# REF_TIMING.net
KiCad netlist of a schematic drawn in Altium Designer
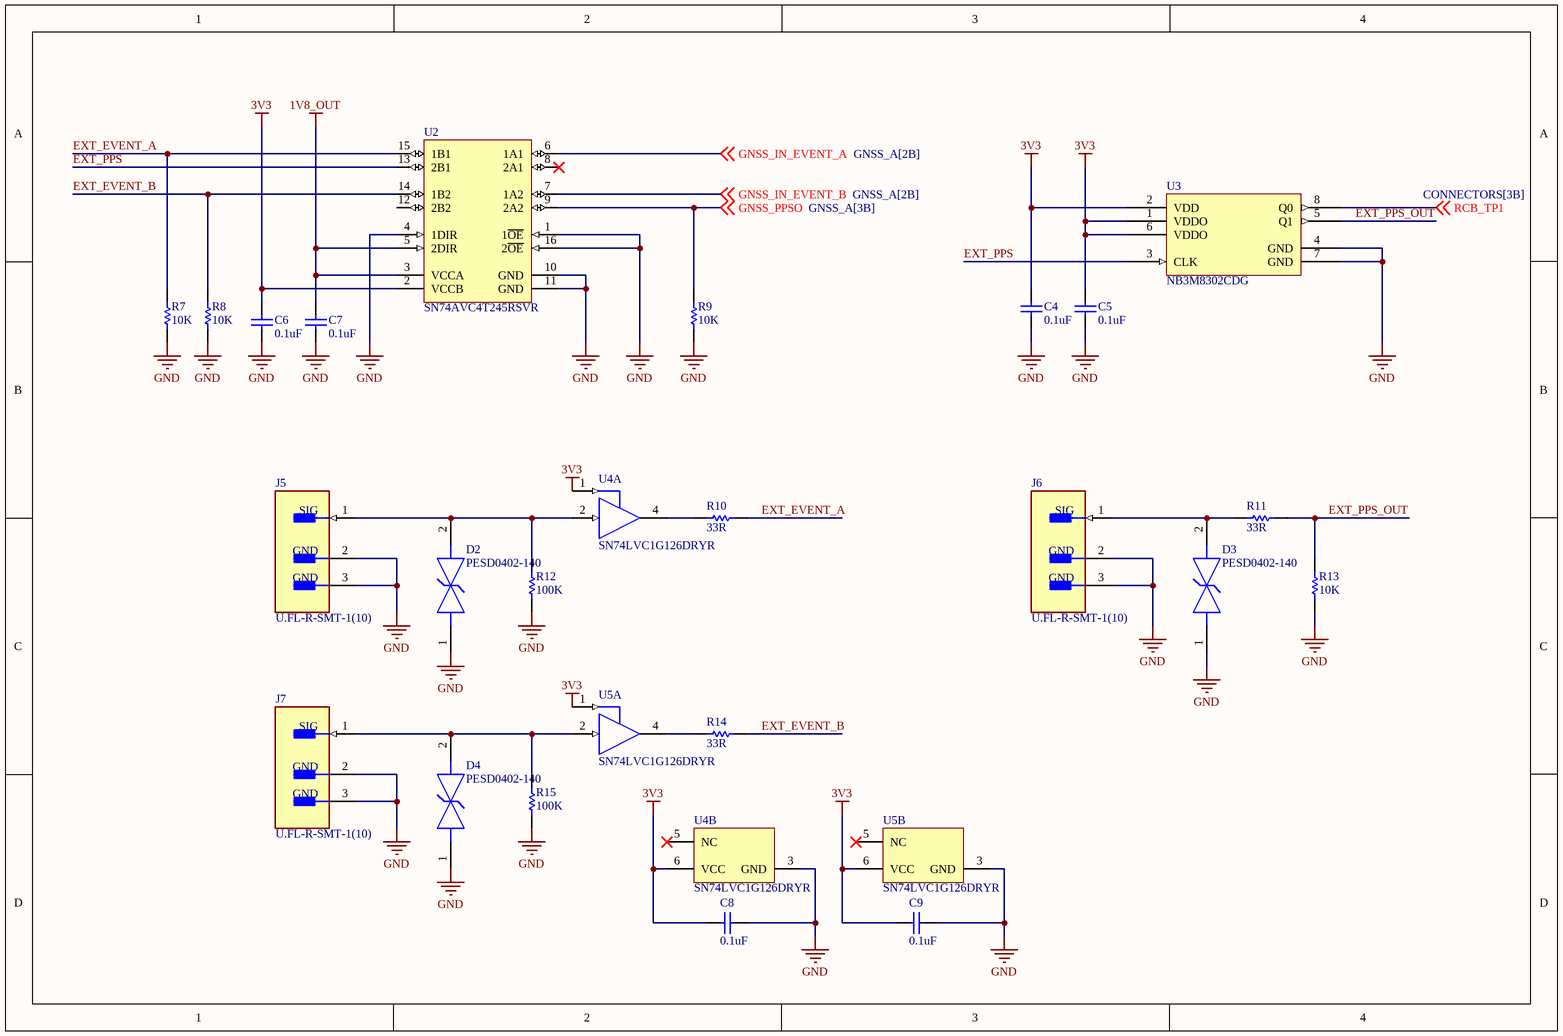
[diagram p0: REF_TIMING.SchDoc]

(export (version "E")
  (design (tool "Eeschema 10.0.6"))
  (components
    (comp (ref "C4")
      (value "0.1uF")
      (footprint "CAPC1005X56X25LL10T15")
      (fields
        (field (name "MANUFACTURER") "AVX Interconnect / Elco")
        (field (name "PART NUMBER") "04026D104KAT2A")
      )
      (libsource (lib "Altium Content Vault") (part "CAP"))
    )
    (comp (ref "C5")
      (value "0.1uF")
      (footprint "CAPC1005X56X25LL10T15")
      (fields
        (field (name "MANUFACTURER") "AVX Interconnect / Elco")
        (field (name "PART NUMBER") "04026D104KAT2A")
      )
      (libsource (lib "Altium Content Vault") (part "CAP"))
    )
    (comp (ref "C6")
      (value "0.1uF")
      (footprint "CAPC1005X56X25LL10T15")
      (fields
        (field (name "MANUFACTURER") "AVX Interconnect / Elco")
        (field (name "PART NUMBER") "04026D104KAT2A")
      )
      (libsource (lib "Altium Content Vault") (part "CAP"))
    )
    (comp (ref "C7")
      (value "0.1uF")
      (footprint "CAPC1005X56X25LL10T15")
      (fields
        (field (name "MANUFACTURER") "AVX Interconnect / Elco")
        (field (name "PART NUMBER") "04026D104KAT2A")
      )
      (libsource (lib "Altium Content Vault") (part "CAP"))
    )
    (comp (ref "C8")
      (value "0.1uF")
      (footprint "CAPC1005X56X25LL10T15")
      (fields
        (field (name "MANUFACTURER") "AVX Interconnect / Elco")
        (field (name "PART NUMBER") "04026D104KAT2A")
      )
      (libsource (lib "Altium Content Vault") (part "CAP"))
    )
    (comp (ref "C9")
      (value "0.1uF")
      (footprint "CAPC1005X56X25LL10T15")
      (fields
        (field (name "MANUFACTURER") "AVX Interconnect / Elco")
        (field (name "PART NUMBER") "04026D104KAT2A")
      )
      (libsource (lib "Altium Content Vault") (part "CAP"))
    )
    (comp (ref "D2")
      (value "PESD0402-140")
      (footprint "FP-PESD0402-MFG")
      (description "TVS DIODE 14V 40V 0402")
      (fields
        (field (name "OCTOPART") "https://octopart.com/pesd0402-140-littelfuse-74215061")
        (field (name "MANUFACTURER") "Littelfuse Inc.")
      )
      (libsource (lib "Altium Content Vault") (part "edccc070dd5cba1f9372128faf3915e"))
    )
    (comp (ref "D3")
      (value "PESD0402-140")
      (footprint "FP-PESD0402-MFG")
      (description "TVS DIODE 14V 40V 0402")
      (fields
        (field (name "OCTOPART") "https://octopart.com/pesd0402-140-littelfuse-74215061")
        (field (name "MANUFACTURER") "Littelfuse Inc.")
      )
      (libsource (lib "Altium Content Vault") (part "edccc070dd5cba1f9372128faf3915e"))
    )
    (comp (ref "D4")
      (value "PESD0402-140")
      (footprint "FP-PESD0402-MFG")
      (description "TVS DIODE 14V 40V 0402")
      (fields
        (field (name "OCTOPART") "https://octopart.com/pesd0402-140-littelfuse-74215061")
        (field (name "MANUFACTURER") "Littelfuse Inc.")
      )
      (libsource (lib "Altium Content Vault") (part "edccc070dd5cba1f9372128faf3915e"))
    )
    (comp (ref "J5")
      (value "U.FL-R-SMT-1(10)")
      (footprint "FP-U_FL-R-SMT-1_10-MFG")
      (description "CONN U.FL RCPT STR 50 OHM SMD")
      (libsource (lib "Altium Content Vault") (part "7158abf7d987fa84906f6fb0d115710"))
    )
    (comp (ref "J6")
      (value "U.FL-R-SMT-1(10)")
      (footprint "FP-U_FL-R-SMT-1_10-MFG")
      (description "CONN U.FL RCPT STR 50 OHM SMD")
      (libsource (lib "Altium Content Vault") (part "7158abf7d987fa84906f6fb0d115710"))
    )
    (comp (ref "J7")
      (value "U.FL-R-SMT-1(10)")
      (footprint "FP-U_FL-R-SMT-1_10-MFG")
      (description "CONN U.FL RCPT STR 50 OHM SMD")
      (libsource (lib "Altium Content Vault") (part "7158abf7d987fa84906f6fb0d115710"))
    )
    (comp (ref "R7")
      (value "10K")
      (footprint "RESC1005X40X25ML05T10")
      (fields (field (name "PART NUMBER") "CRCW040210K0FKEDHP") (field (name "MANUFACTURER") "Vishay Dale"))
      (libsource (lib "Altium Content Vault") (part "RES"))
    )
    (comp (ref "R8")
      (value "10K")
      (footprint "RESC1005X40X25ML05T10")
      (fields (field (name "PART NUMBER") "CRCW040210K0FKEDHP") (field (name "MANUFACTURER") "Vishay Dale"))
      (libsource (lib "Altium Content Vault") (part "RES"))
    )
    (comp (ref "R9")
      (value "10K")
      (footprint "RESC1005X40X25ML05T10")
      (fields (field (name "PART NUMBER") "CRCW040210K0FKEDHP") (field (name "MANUFACTURER") "Vishay Dale"))
      (libsource (lib "Altium Content Vault") (part "RES"))
    )
    (comp (ref "R10")
      (value "33R")
      (footprint "RESC1005X40X25LL05T10")
      (fields (field (name "PART NUMBER") "RC0402FR-0733RL") (field (name "MANUFACTURER") "Yageo / Phycomp"))
      (libsource (lib "Altium Content Vault") (part "RES"))
    )
    (comp (ref "R11")
      (value "33R")
      (footprint "RESC1005X40X25LL05T10")
      (fields (field (name "PART NUMBER") "RC0402FR-0733RL") (field (name "MANUFACTURER") "Yageo / Phycomp"))
      (libsource (lib "Altium Content Vault") (part "RES"))
    )
    (comp (ref "R12")
      (value "100K")
      (footprint "RESC1005X40X25NL05T10")
      (fields (field (name "PART NUMBER") "RC0402FR-07100KL") (field (name "MANUFACTURER") "Yageo / Phycomp"))
      (libsource (lib "Altium Content Vault") (part "RES"))
    )
    (comp (ref "R13")
      (value "10K")
      (footprint "RESC1005X40X25ML05T10")
      (fields (field (name "PART NUMBER") "CRCW040210K0FKEDHP") (field (name "MANUFACTURER") "Vishay Dale"))
      (libsource (lib "Altium Content Vault") (part "RES"))
    )
    (comp (ref "R14")
      (value "33R")
      (footprint "RESC1005X40X25LL05T10")
      (fields (field (name "PART NUMBER") "RC0402FR-0733RL") (field (name "MANUFACTURER") "Yageo / Phycomp"))
      (libsource (lib "Altium Content Vault") (part "RES"))
    )
    (comp (ref "R15")
      (value "100K")
      (footprint "RESC1005X40X25NL05T10")
      (fields (field (name "PART NUMBER") "RC0402FR-07100KL") (field (name "MANUFACTURER") "Yageo / Phycomp"))
      (libsource (lib "Altium Content Vault") (part "RES"))
    )
    (comp (ref "U2")
      (value "SN74AVC4T245RSVR")
      (footprint "RSV0016A_V")
      (fields (field (name "MANUFACTURER") "Texas Instruments"))
      (libsource (lib "Altium Content Vault") (part "TI-SN74AVC4T245-UQFN-16"))
    )
    (comp (ref "U3")
      (value "NB3M8302CDG")
      (footprint "SOIC8_ONS")
      (description "No Description Available")
      (fields (field (name "COPYRIGHT") "Copyright (C) 2023 Ultra Librarian. All rights reserved."))
      (libsource (lib "NB3M8302CDG") (part "NB3M8302CDG"))
    )
    (comp (ref "U4")
      (value "SN74LVC1G126DRYR")
      (footprint "DRY0006A_V")
      (description "Single Bus Buffer Gate With 3-State Outputs, DRY0006A, LARGE T&R")
      (fields
        (field (name "MANUFACTURER") "Texas Instruments")
        (field (name "GENERIC PART NUMBER") "SN74LVC1G126")
      )
      (libsource (lib "Altium Content Vault") (part "TI-SN74XXX1G126-6"))
    )
    (comp (ref "U5")
      (value "SN74LVC1G126DRYR")
      (footprint "DRY0006A_V")
      (description "Single Bus Buffer Gate With 3-State Outputs, DRY0006A, LARGE T&R")
      (fields
        (field (name "MANUFACTURER") "Texas Instruments")
        (field (name "GENERIC PART NUMBER") "SN74LVC1G126")
      )
      (libsource (lib "Altium Content Vault") (part "TI-SN74XXX1G126-6"))
    )
  )
  (nets
    (net (code "1") (name "/EXT_EVENT_A") (class "Default")
      (node (ref "R10") (pin "2") (pinfunction "2_2") (pintype "passive"))
      (node (ref "R7") (pin "2") (pinfunction "2_2") (pintype "passive"))
      (node (ref "U2") (pin "15") (pinfunction "1B1_15") (pintype "bidirectional"))
    )
    (net (code "2") (name "/EXT_EVENT_B") (class "Default")
      (node (ref "R14") (pin "2") (pinfunction "2_2") (pintype "passive"))
      (node (ref "R8") (pin "2") (pinfunction "2_2") (pintype "passive"))
      (node (ref "U2") (pin "14") (pinfunction "1B2_14") (pintype "bidirectional"))
    )
    (net (code "3") (name "/EXT_PPS") (class "Default")
      (node (ref "U2") (pin "13") (pinfunction "2B1_13") (pintype "bidirectional"))
      (node (ref "U3") (pin "3") (pinfunction "CLK_3") (pintype "input"))
    )
    (net (code "4") (name "/EXT_PPS_OUT") (class "Default")
      (node (ref "R11") (pin "2") (pinfunction "2_2") (pintype "passive"))
      (node (ref "R13") (pin "2") (pinfunction "2_2") (pintype "passive"))
      (node (ref "U3") (pin "5") (pinfunction "Q1_5") (pintype "output"))
    )
    (net (code "5") (name "1V8_OUT") (class "Default")
      (node (ref "C7") (pin "2") (pinfunction "2_2") (pintype "passive"))
      (node (ref "U2") (pin "3") (pinfunction "VCCA_3") (pintype "power_in"))
      (node (ref "U2") (pin "5") (pinfunction "2DIR_5") (pintype "input"))
    )
    (net (code "6") (name "3V3") (class "Default")
      (node (ref "C4") (pin "1") (pinfunction "1_1") (pintype "passive"))
      (node (ref "C5") (pin "1") (pinfunction "1_1") (pintype "passive"))
      (node (ref "C6") (pin "2") (pinfunction "2_2") (pintype "passive"))
      (node (ref "C8") (pin "2") (pinfunction "2_2") (pintype "passive"))
      (node (ref "C9") (pin "2") (pinfunction "2_2") (pintype "passive"))
      (node (ref "U2") (pin "2") (pinfunction "VCCB_2") (pintype "power_in"))
      (node (ref "U3") (pin "1") (pinfunction "VDDO_1") (pintype "power_in"))
      (node (ref "U3") (pin "2") (pinfunction "VDD_2") (pintype "power_in"))
      (node (ref "U3") (pin "6") (pinfunction "VDDO_6") (pintype "power_in"))
      (node (ref "U4") (pin "1") (pinfunction "OE_1") (pintype "input"))
      (node (ref "U4") (pin "6") (pinfunction "VCC_6") (pintype "power_in"))
      (node (ref "U5") (pin "1") (pinfunction "OE_1") (pintype "input"))
      (node (ref "U5") (pin "6") (pinfunction "VCC_6") (pintype "power_in"))
    )
    (net (code "7") (name "GND") (class "Default")
      (node (ref "C4") (pin "2") (pinfunction "2_2") (pintype "passive"))
      (node (ref "C5") (pin "2") (pinfunction "2_2") (pintype "passive"))
      (node (ref "C6") (pin "1") (pinfunction "1_1") (pintype "passive"))
      (node (ref "C7") (pin "1") (pinfunction "1_1") (pintype "passive"))
      (node (ref "C8") (pin "1") (pinfunction "1_1") (pintype "passive"))
      (node (ref "C9") (pin "1") (pinfunction "1_1") (pintype "passive"))
      (node (ref "D2") (pin "1") (pinfunction "1_1") (pintype "passive"))
      (node (ref "D3") (pin "1") (pinfunction "1_1") (pintype "passive"))
      (node (ref "D4") (pin "1") (pinfunction "1_1") (pintype "passive"))
      (node (ref "J5") (pin "2") (pinfunction "GND_2") (pintype "power_in"))
      (node (ref "J5") (pin "3") (pinfunction "GND_3") (pintype "power_in"))
      (node (ref "J6") (pin "2") (pinfunction "GND_2") (pintype "power_in"))
      (node (ref "J6") (pin "3") (pinfunction "GND_3") (pintype "power_in"))
      (node (ref "J7") (pin "2") (pinfunction "GND_2") (pintype "power_in"))
      (node (ref "J7") (pin "3") (pinfunction "GND_3") (pintype "power_in"))
      (node (ref "R12") (pin "1") (pinfunction "1_1") (pintype "passive"))
      (node (ref "R13") (pin "1") (pinfunction "1_1") (pintype "passive"))
      (node (ref "R15") (pin "1") (pinfunction "1_1") (pintype "passive"))
      (node (ref "R7") (pin "1") (pinfunction "1_1") (pintype "passive"))
      (node (ref "R8") (pin "1") (pinfunction "1_1") (pintype "passive"))
      (node (ref "R9") (pin "1") (pinfunction "1_1") (pintype "passive"))
      (node (ref "U2") (pin "1") (pinfunction "1~{OE}_1") (pintype "input"))
      (node (ref "U2") (pin "10") (pinfunction "GND_10") (pintype "power_in"))
      (node (ref "U2") (pin "11") (pinfunction "GND_11") (pintype "power_in"))
      (node (ref "U2") (pin "16") (pinfunction "2~{OE}_16") (pintype "input"))
      (node (ref "U2") (pin "4") (pinfunction "1DIR_4") (pintype "input"))
      (node (ref "U3") (pin "4") (pinfunction "GND_4") (pintype "power_in"))
      (node (ref "U3") (pin "7") (pinfunction "GND_7") (pintype "power_in"))
      (node (ref "U4") (pin "3") (pinfunction "GND_3") (pintype "power_in"))
      (node (ref "U5") (pin "3") (pinfunction "GND_3") (pintype "power_in"))
    )
    (net (code "8") (name "GNSS_IN_EVENT_A") (class "Default")
      (node (ref "U2") (pin "6") (pinfunction "1A1_6") (pintype "bidirectional"))
    )
    (net (code "9") (name "GNSS_IN_EVENT_B") (class "Default")
      (node (ref "U2") (pin "7") (pinfunction "1A2_7") (pintype "bidirectional"))
    )
    (net (code "10") (name "GNSS_PPSO") (class "Default")
      (node (ref "R9") (pin "2") (pinfunction "2_2") (pintype "passive"))
      (node (ref "U2") (pin "9") (pinfunction "2A2_9") (pintype "bidirectional"))
    )
    (net (code "11") (name "Net-(J5-SIG)") (class "Default")
      (node (ref "D2") (pin "2") (pinfunction "2_2") (pintype "passive"))
      (node (ref "J5") (pin "1") (pinfunction "SIG_1") (pintype "input"))
      (node (ref "R12") (pin "2") (pinfunction "2_2") (pintype "passive"))
      (node (ref "U4") (pin "2") (pinfunction "A_2") (pintype "input"))
    )
    (net (code "12") (name "Net-(J6-SIG)") (class "Default")
      (node (ref "D3") (pin "2") (pinfunction "2_2") (pintype "passive"))
      (node (ref "J6") (pin "1") (pinfunction "SIG_1") (pintype "input"))
      (node (ref "R11") (pin "1") (pinfunction "1_1") (pintype "passive"))
    )
    (net (code "13") (name "Net-(J7-SIG)") (class "Default")
      (node (ref "D4") (pin "2") (pinfunction "2_2") (pintype "passive"))
      (node (ref "J7") (pin "1") (pinfunction "SIG_1") (pintype "input"))
      (node (ref "R15") (pin "2") (pinfunction "2_2") (pintype "passive"))
      (node (ref "U5") (pin "2") (pinfunction "A_2") (pintype "input"))
    )
    (net (code "14") (name "Net-(U4A-Y)") (class "Default")
      (node (ref "R10") (pin "1") (pinfunction "1_1") (pintype "passive"))
      (node (ref "U4") (pin "4") (pinfunction "Y_4") (pintype "tri_state"))
    )
    (net (code "15") (name "Net-(U5A-Y)") (class "Default")
      (node (ref "R14") (pin "1") (pinfunction "1_1") (pintype "passive"))
      (node (ref "U5") (pin "4") (pinfunction "Y_4") (pintype "tri_state"))
    )
    (net (code "16") (name "RCB_TP1") (class "Default")
      (node (ref "U3") (pin "8") (pinfunction "Q0_8") (pintype "output"))
    )
    (net (code "17") (name "unconnected-(U2-2A1-Pad8)") (class "Default")
      (node (ref "U2") (pin "8") (pinfunction "2A1_8") (pintype "bidirectional+no_connect"))
    )
    (net (code "18") (name "unconnected-(U2-2B2-Pad12)") (class "Default")
      (node (ref "U2") (pin "12") (pinfunction "2B2_12") (pintype "bidirectional"))
    )
    (net (code "19") (name "unconnected-(U4B-NC-Pad5)") (class "Default")
      (node (ref "U4") (pin "5") (pinfunction "NC_5") (pintype "passive+no_connect"))
    )
    (net (code "20") (name "unconnected-(U5B-NC-Pad5)") (class "Default")
      (node (ref "U5") (pin "5") (pinfunction "NC_5") (pintype "passive+no_connect"))
    )
  )
)
